# CAN_Breakout.net
KiCad netlist of a schematic drawn in Altium Designer
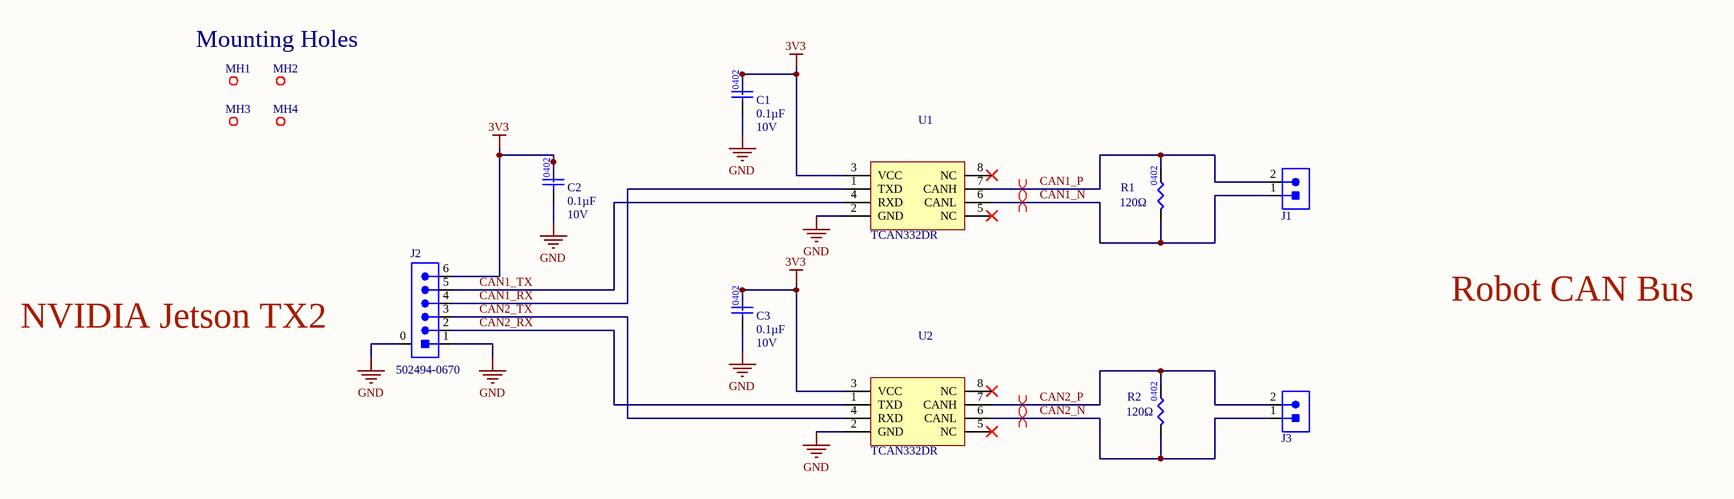
[diagram p0: CAN Breakout.SchDoc]

(export (version "E")
  (design (tool "Eeschema 10.0.6"))
  (components
    (comp (ref "C1")
      (value "0.1µF")
      (footprint "CAP0402")
      (description "CAP CER 0.1UF 10V X7R 0402")
      (fields (field (name "VOLTAGE RATING") "10V") (field (name "Comment") "CAP_0.1uF_10V_0402"))
      (libsource (lib "UWRT_Schematic_Library_2020") (part "CAP_0.1uF_10V_0402"))
    )
    (comp (ref "C2")
      (value "0.1µF")
      (footprint "CAP0402")
      (description "CAP CER 0.1UF 10V X7R 0402")
      (fields (field (name "VOLTAGE RATING") "10V") (field (name "Comment") "CAP_0.1uF_10V_0402"))
      (libsource (lib "UWRT_Schematic_Library_2020") (part "CAP_0.1uF_10V_0402"))
    )
    (comp (ref "C3")
      (value "0.1µF")
      (footprint "CAP0402")
      (description "CAP CER 0.1UF 10V X7R 0402")
      (fields (field (name "VOLTAGE RATING") "10V") (field (name "Comment") "CAP_0.1uF_10V_0402"))
      (libsource (lib "UWRT_Schematic_Library_2020") (part "CAP_0.1uF_10V_0402"))
    )
    (comp (ref "J1")
      (value "CON_2POS_SCREW_TERM")
      (footprint "1935161")
      (description "TERM BLK 2POS SIDE ENTRY 5MM")
      (libsource (lib "UWRT_Schematic_Library_2020") (part "CON_2POS_SCREW_TERM"))
    )
    (comp (ref "J2")
      (value "CON_6M_SM_RA")
      (footprint "MOLEX-5024940670")
      (description "CONN HEADER SMD RIGHT ANGLE 2MM PITCH")
      (fields (field (name "MANUFACTURER PART NUMBER 1") "502494-0670"))
      (libsource (lib "UWRT_Schematic_Library_2020") (part "CON_6M_SM_RA"))
    )
    (comp (ref "J3")
      (value "CON_2POS_SCREW_TERM")
      (footprint "1935161")
      (description "TERM BLK 2POS SIDE ENTRY 5MM")
      (libsource (lib "UWRT_Schematic_Library_2020") (part "CON_2POS_SCREW_TERM"))
    )
    (comp (ref "MH1")
      (value "MOUNTING_HOLE_M3")
      (footprint "MOUNTING_HOLE_3mm")
      (libsource (lib "UWRT_Schematic_Library_2020") (part "MOUNTING_HOLE_M3"))
    )
    (comp (ref "MH2")
      (value "MOUNTING_HOLE_M3")
      (footprint "MOUNTING_HOLE_3mm")
      (libsource (lib "UWRT_Schematic_Library_2020") (part "MOUNTING_HOLE_M3"))
    )
    (comp (ref "MH3")
      (value "MOUNTING_HOLE_M3")
      (footprint "MOUNTING_HOLE_3mm")
      (libsource (lib "UWRT_Schematic_Library_2020") (part "MOUNTING_HOLE_M3"))
    )
    (comp (ref "MH4")
      (value "MOUNTING_HOLE_M3")
      (footprint "MOUNTING_HOLE_3mm")
      (libsource (lib "UWRT_Schematic_Library_2020") (part "MOUNTING_HOLE_M3"))
    )
    (comp (ref "R1")
      (value "120Ω")
      (footprint "RES0402")
      (description "RES 120 OHM 5% 1/16W 0402")
      (fields (field (name "POWER") "1/16W") (field (name "TOLERANCE") "5%"))
      (libsource (lib "UWRT_Schematic_Library_2020") (part "RES_120Ω_0402_5%"))
    )
    (comp (ref "R2")
      (value "120Ω")
      (footprint "RES0402")
      (description "RES 120 OHM 5% 1/16W 0402")
      (fields (field (name "POWER") "1/16W") (field (name "TOLERANCE") "5%"))
      (libsource (lib "UWRT_Schematic_Library_2020") (part "RES_120Ω_0402_5%"))
    )
    (comp (ref "U1")
      (value "TCAN332DR")
      (footprint "SOIC127P599X175-8N")
      (description "IC CAN TRANSCEIVER")
      (libsource (lib "UWRT_Schematic_Library_2020") (part "TCAN332DR"))
    )
    (comp (ref "U2")
      (value "TCAN332DR")
      (footprint "SOIC127P599X175-8N")
      (description "IC CAN TRANSCEIVER")
      (libsource (lib "UWRT_Schematic_Library_2020") (part "TCAN332DR"))
    )
  )
  (nets
    (net (code "1") (name "/CAN1_N") (class "Default")
      (node (ref "J1") (pin "1") (pinfunction "1_1") (pintype "passive"))
      (node (ref "R1") (pin "1") (pinfunction "1_1") (pintype "passive"))
      (node (ref "U1") (pin "6") (pinfunction "CANL_6") (pintype "passive"))
    )
    (net (code "2") (name "/CAN1_P") (class "Default")
      (node (ref "J1") (pin "2") (pinfunction "2_2") (pintype "passive"))
      (node (ref "R1") (pin "2") (pinfunction "2_2") (pintype "passive"))
      (node (ref "U1") (pin "7") (pinfunction "CANH_7") (pintype "passive"))
    )
    (net (code "3") (name "/CAN1_RX") (class "Default")
      (node (ref "J2") (pin "4") (pinfunction "4_4") (pintype "passive"))
      (node (ref "U1") (pin "1") (pinfunction "TXD_1") (pintype "passive"))
    )
    (net (code "4") (name "/CAN1_TX") (class "Default")
      (node (ref "J2") (pin "5") (pinfunction "5_5") (pintype "passive"))
      (node (ref "U1") (pin "4") (pinfunction "RXD_4") (pintype "passive"))
    )
    (net (code "5") (name "/CAN2_N") (class "Default")
      (node (ref "J3") (pin "1") (pinfunction "1_1") (pintype "passive"))
      (node (ref "R2") (pin "1") (pinfunction "1_1") (pintype "passive"))
      (node (ref "U2") (pin "6") (pinfunction "CANL_6") (pintype "passive"))
    )
    (net (code "6") (name "/CAN2_P") (class "Default")
      (node (ref "J3") (pin "2") (pinfunction "2_2") (pintype "passive"))
      (node (ref "R2") (pin "2") (pinfunction "2_2") (pintype "passive"))
      (node (ref "U2") (pin "7") (pinfunction "CANH_7") (pintype "passive"))
    )
    (net (code "7") (name "/CAN2_RX") (class "Default")
      (node (ref "J2") (pin "2") (pinfunction "2_2") (pintype "passive"))
      (node (ref "U2") (pin "1") (pinfunction "TXD_1") (pintype "passive"))
    )
    (net (code "8") (name "/CAN2_TX") (class "Default")
      (node (ref "J2") (pin "3") (pinfunction "3_3") (pintype "passive"))
      (node (ref "U2") (pin "4") (pinfunction "RXD_4") (pintype "passive"))
    )
    (net (code "9") (name "3V3") (class "Default")
      (node (ref "C1") (pin "2") (pinfunction "2_2") (pintype "passive"))
      (node (ref "C2") (pin "2") (pinfunction "2_2") (pintype "passive"))
      (node (ref "C3") (pin "2") (pinfunction "2_2") (pintype "passive"))
      (node (ref "J2") (pin "6") (pinfunction "6_6") (pintype "passive"))
      (node (ref "U1") (pin "3") (pinfunction "VCC_3") (pintype "passive"))
      (node (ref "U2") (pin "3") (pinfunction "VCC_3") (pintype "passive"))
    )
    (net (code "10") (name "GND") (class "Default")
      (node (ref "C1") (pin "1") (pinfunction "1_1") (pintype "passive"))
      (node (ref "C2") (pin "1") (pinfunction "1_1") (pintype "passive"))
      (node (ref "C3") (pin "1") (pinfunction "1_1") (pintype "passive"))
      (node (ref "J2") (pin "0") (pinfunction "0_0") (pintype "passive"))
      (node (ref "J2") (pin "1") (pinfunction "1_1") (pintype "passive"))
      (node (ref "U1") (pin "2") (pinfunction "GND_2") (pintype "passive"))
      (node (ref "U2") (pin "2") (pinfunction "GND_2") (pintype "passive"))
    )
    (net (code "11") (name "unconnected-(U1-NC-Pad5)") (class "Default")
      (node (ref "U1") (pin "5") (pinfunction "NC_5") (pintype "passive+no_connect"))
    )
    (net (code "12") (name "unconnected-(U1-NC-Pad8)") (class "Default")
      (node (ref "U1") (pin "8") (pinfunction "NC_8") (pintype "passive+no_connect"))
    )
    (net (code "13") (name "unconnected-(U2-NC-Pad5)") (class "Default")
      (node (ref "U2") (pin "5") (pinfunction "NC_5") (pintype "passive+no_connect"))
    )
    (net (code "14") (name "unconnected-(U2-NC-Pad8)") (class "Default")
      (node (ref "U2") (pin "8") (pinfunction "NC_8") (pintype "passive+no_connect"))
    )
  )
)
